# power.net
KiCad netlist of a schematic drawn in Altium Designer
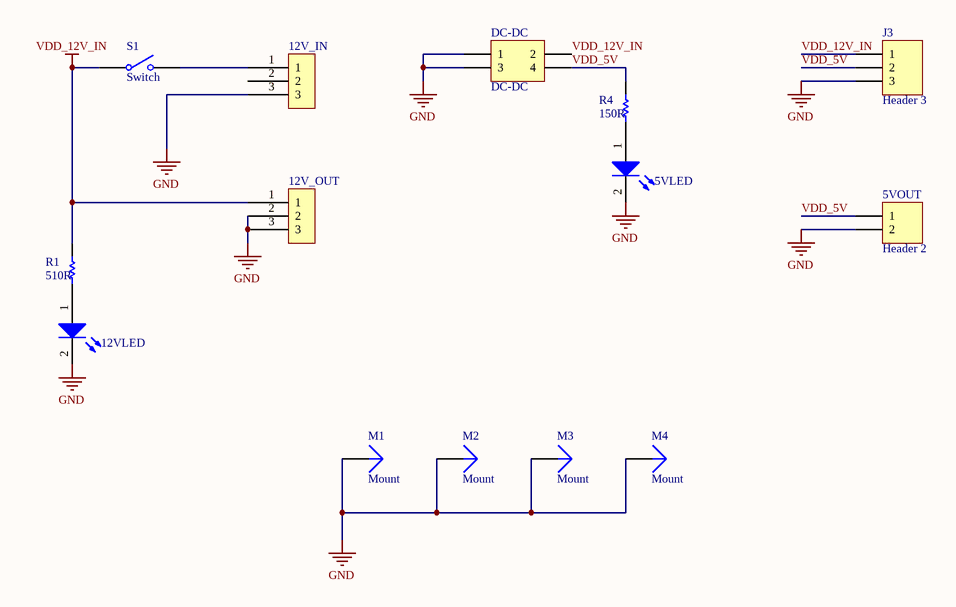
[diagram p0: power.SchDoc]

(export (version "E")
  (design (tool "Eeschema 10.0.6"))
  (components
    (comp (ref "5VLED")
      (value "5V LED")
      (footprint "0805D")
      (description "RED")
      (fields
        (field (name "MANUFACTURER") "Generic Components")
        (field (name "PUBLISHER") "Altium Hobart Technology Centre")
      )
      (libsource (lib "Miscellaneous Devices") (part "LED2"))
    )
    (comp (ref "5VOUT")
      (value "Header 2")
      (footprint "HDR1X2")
      (description "Header, 2-Pin")
      (fields (field (name "PUBLISHER") "Altium Limited"))
      (libsource (lib "Miscellaneous Connectors") (part "Header 2"))
    )
    (comp (ref "12VLED")
      (value "12V LED")
      (footprint "0805D")
      (description "RED")
      (fields
        (field (name "MANUFACTURER") "Generic Components")
        (field (name "PUBLISHER") "Altium Hobart Technology Centre")
      )
      (libsource (lib "Miscellaneous Devices") (part "LED2"))
    )
    (comp (ref "12V_IN")
      (value "12V IN")
      (footprint "PW_PORT")
      (libsource (lib "Miscellaneous Connectors") (part "CON3"))
    )
    (comp (ref "12V_OUT") (value "12V OUT") (footprint "PW_PORT") (libsource (lib "EP3C25") (part "CON3")))
    (comp (ref "DC-DC")
      (value "DC-DC")
      (footprint "DC-DC5V_HDR2*2")
      (description "Header, 2-Pin, Dual row")
      (fields (field (name "PUBLISHER") "Altium Limited"))
      (libsource (lib "Miscellaneous Connectors") (part "Header 2X2"))
    )
    (comp (ref "J3")
      (value "Header 3")
      (footprint "HDR1X3")
      (description "Header, 3-Pin")
      (fields (field (name "PUBLISHER") "Altium Limited"))
      (libsource (lib "Miscellaneous Connectors") (part "Header 3"))
    )
    (comp (ref "M1")
      (value "Mount")
      (footprint "安装孔-3.5-5")
      (description "Plug")
      (fields (field (name "PUBLISHER") "Altium Limited"))
      (libsource (lib "Miscellaneous Connectors") (part "Plug"))
    )
    (comp (ref "M2")
      (value "Mount")
      (footprint "安装孔-3.5-5")
      (description "Plug")
      (fields (field (name "PUBLISHER") "Altium Limited"))
      (libsource (lib "Miscellaneous Connectors") (part "Plug"))
    )
    (comp (ref "M3")
      (value "Mount")
      (footprint "安装孔-3.5-5")
      (description "Plug")
      (fields (field (name "PUBLISHER") "Altium Limited"))
      (libsource (lib "Miscellaneous Connectors") (part "Plug"))
    )
    (comp (ref "M4")
      (value "Mount")
      (footprint "安装孔-3.5-5")
      (description "Plug")
      (fields (field (name "PUBLISHER") "Altium Limited"))
      (libsource (lib "Miscellaneous Connectors") (part "Plug"))
    )
    (comp (ref "R1")
      (value "510R")
      (footprint "0805R")
      (description "Resistor")
      (fields
        (field (name "MANUFACTURER") "Generic Components")
        (field (name "PUBLISHER") "Altium Hobart Technology Centre")
      )
      (libsource (lib "HAIBAO_MEGAV1.0_1") (part "Res1"))
    )
    (comp (ref "R4")
      (value "150R")
      (footprint "0805R")
      (description "Resistor")
      (fields
        (field (name "MANUFACTURER") "Generic Components")
        (field (name "PUBLISHER") "Altium Hobart Technology Centre")
      )
      (libsource (lib "HAIBAO_MEGAV1.0_1") (part "Res1"))
    )
    (comp (ref "S1")
      (value "Switch")
      (footprint "PW_KCD2115")
      (description "Single-Pole, Single-Throw Switch")
      (fields (field (name "PUBLISHER") "Altium Limited"))
      (libsource (lib "Miscellaneous Devices") (part "SW-SPST"))
    )
  )
  (nets
    (net (code "1") (name "/VDD_5V") (class "Default")
      (node (ref "5VOUT") (pin "1") (pinfunction "1_1") (pintype "passive"))
      (node (ref "DC-DC") (pin "4") (pinfunction "4_4") (pintype "passive"))
      (node (ref "J3") (pin "2") (pinfunction "2_2") (pintype "passive"))
      (node (ref "R4") (pin "2") (pinfunction "2_2") (pintype "passive"))
    )
    (net (code "2") (name "GND") (class "Default")
      (node (ref "12VLED") (pin "2") (pinfunction "K_2") (pintype "passive"))
      (node (ref "12V_IN") (pin "3") (pinfunction "3_3") (pintype "passive"))
      (node (ref "12V_OUT") (pin "2") (pinfunction "2_2") (pintype "passive"))
      (node (ref "12V_OUT") (pin "3") (pinfunction "3_3") (pintype "passive"))
      (node (ref "5VLED") (pin "2") (pinfunction "K_2") (pintype "passive"))
      (node (ref "5VOUT") (pin "2") (pinfunction "2_2") (pintype "passive"))
      (node (ref "DC-DC") (pin "1") (pinfunction "1_1") (pintype "passive"))
      (node (ref "DC-DC") (pin "3") (pinfunction "3_3") (pintype "passive"))
      (node (ref "J3") (pin "3") (pinfunction "3_3") (pintype "passive"))
      (node (ref "M1") (pin "1") (pinfunction "1_1") (pintype "passive"))
      (node (ref "M2") (pin "1") (pinfunction "1_1") (pintype "passive"))
      (node (ref "M3") (pin "1") (pinfunction "1_1") (pintype "passive"))
      (node (ref "M4") (pin "1") (pinfunction "1_1") (pintype "passive"))
    )
    (net (code "3") (name "Net-(5VLED-A)") (class "Default")
      (node (ref "5VLED") (pin "1") (pinfunction "A_1") (pintype "passive"))
      (node (ref "R4") (pin "1") (pinfunction "1_1") (pintype "passive"))
    )
    (net (code "4") (name "Net-(12VLED-A)") (class "Default")
      (node (ref "12VLED") (pin "1") (pinfunction "A_1") (pintype "passive"))
      (node (ref "R1") (pin "1") (pinfunction "1_1") (pintype "passive"))
    )
    (net (code "5") (name "Net-(S1-NO)") (class "Default")
      (node (ref "12V_IN") (pin "1") (pinfunction "1_1") (pintype "passive"))
      (node (ref "S1") (pin "2") (pinfunction "NO_2") (pintype "passive"))
    )
    (net (code "6") (name "VDD_12V_IN") (class "Default")
      (node (ref "12V_OUT") (pin "1") (pinfunction "1_1") (pintype "passive"))
      (node (ref "DC-DC") (pin "2") (pinfunction "2_2") (pintype "passive"))
      (node (ref "J3") (pin "1") (pinfunction "1_1") (pintype "passive"))
      (node (ref "R1") (pin "2") (pinfunction "2_2") (pintype "passive"))
      (node (ref "S1") (pin "1") (pinfunction "COMMON_1") (pintype "passive"))
    )
    (net (code "7") (name "unconnected-(12V_IN-Pad2)") (class "Default")
      (node (ref "12V_IN") (pin "2") (pinfunction "2_2") (pintype "passive"))
    )
  )
)
